# Sheet1.net
KiCad netlist of a schematic drawn in Altium Designer
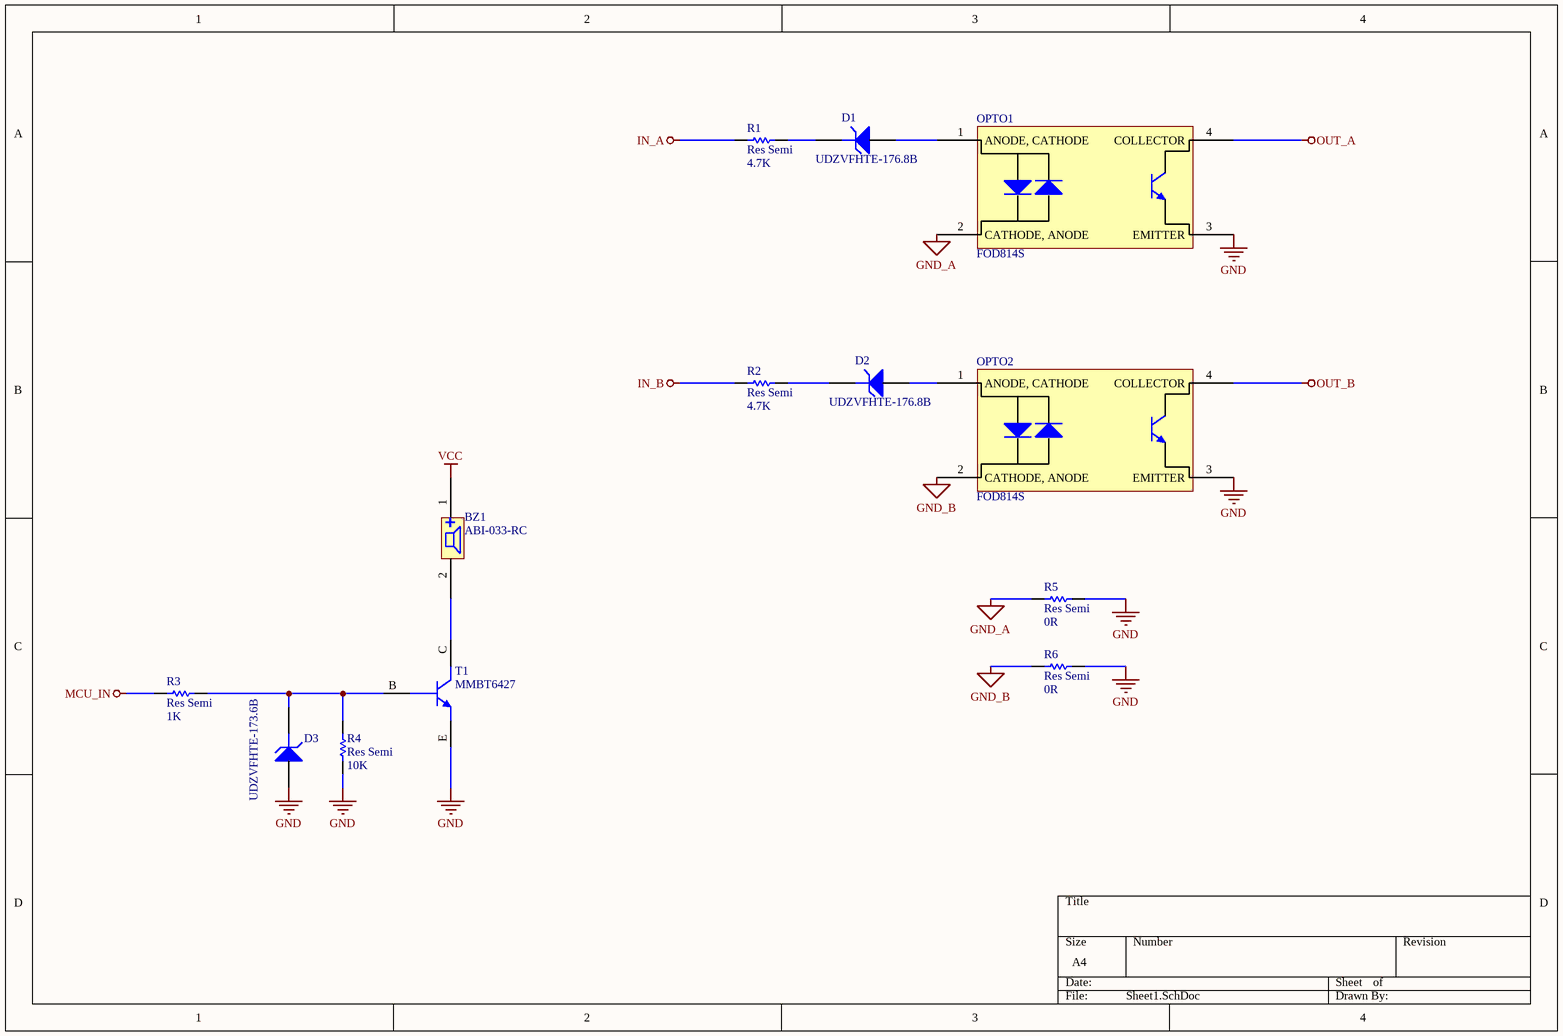
[diagram p0: Sheet1.SchDoc]

(export (version "E")
  (design (tool "Eeschema 10.0.6"))
  (components
    (comp (ref "BZ1")
      (value "ABI-033-RC")
      (footprint "ABI-033-RC")
      (fields (field (name "MANUFACTURER") "PRO SIGNAL"))
      (libsource (lib "BK4000TGLibraries") (part "ABI-033-RC"))
    )
    (comp (ref "D1")
      (value "UDZVFHTE-176.8B")
      (footprint "UDZVFHTE-176.8B")
      (libsource (lib "BK4000TGLibraries") (part "UDZVFHTE-176.8B"))
    )
    (comp (ref "D2")
      (value "UDZVFHTE-176.8B")
      (footprint "UDZVFHTE-176.8B")
      (libsource (lib "BK4000TGLibraries") (part "UDZVFHTE-176.8B"))
    )
    (comp (ref "D3")
      (value "UDZVFHTE-173.6B")
      (footprint "UDZVFHTE-176.8B")
      (libsource (lib "BK4000TGLibraries") (part "UDZVFHTE-176.8B"))
    )
    (comp (ref "OPTO1")
      (value "FOD814S")
      (footprint "FOD814")
      (description "AC Phototransistor Optocoupler")
      (fields (field (name "MANUFACTURER") "Fairchild Semiconductor"))
      (libsource (lib "FOD814") (part "FOD814S"))
    )
    (comp (ref "OPTO2")
      (value "FOD814S")
      (footprint "FOD814")
      (description "AC Phototransistor Optocoupler")
      (fields (field (name "MANUFACTURER") "Fairchild Semiconductor"))
      (libsource (lib "FOD814") (part "FOD814S"))
    )
    (comp (ref "R1")
      (value "Res Semi")
      (footprint "2012[0805]")
      (description "Semiconductor Resistor")
      (fields (field (name "ALTIUM_VALUE") "4.7K") (field (name "PUBLISHER") "Altium Limited"))
      (libsource (lib "Miscellaneous Devices") (part "Res Semi"))
    )
    (comp (ref "R2")
      (value "Res Semi")
      (footprint "2012[0805]")
      (description "Semiconductor Resistor")
      (fields (field (name "ALTIUM_VALUE") "4.7K") (field (name "PUBLISHER") "Altium Limited"))
      (libsource (lib "Miscellaneous Devices") (part "Res Semi"))
    )
    (comp (ref "R3")
      (value "Res Semi")
      (footprint "2012[0805]")
      (description "Semiconductor Resistor")
      (fields (field (name "ALTIUM_VALUE") "1K") (field (name "PUBLISHER") "Altium Limited"))
      (libsource (lib "Miscellaneous Devices") (part "Res Semi"))
    )
    (comp (ref "R4")
      (value "Res Semi")
      (footprint "2012[0805]")
      (description "Semiconductor Resistor")
      (fields (field (name "ALTIUM_VALUE") "10K") (field (name "PUBLISHER") "Altium Limited"))
      (libsource (lib "Miscellaneous Devices") (part "Res Semi"))
    )
    (comp (ref "R5")
      (value "Res Semi")
      (footprint "2012[0805]")
      (description "Semiconductor Resistor")
      (fields (field (name "ALTIUM_VALUE") "0R") (field (name "PUBLISHER") "Altium Limited"))
      (libsource (lib "Miscellaneous Devices") (part "Res Semi"))
    )
    (comp (ref "R6")
      (value "Res Semi")
      (footprint "2012[0805]")
      (description "Semiconductor Resistor")
      (fields (field (name "ALTIUM_VALUE") "0R") (field (name "PUBLISHER") "Altium Limited"))
      (libsource (lib "Miscellaneous Devices") (part "Res Semi"))
    )
    (comp (ref "T1")
      (value "MMBT6427")
      (footprint "MMBT6427")
      (fields (field (name "MANUFACTURER") "ON SEMICONDUCTOR/FAIRCHILD"))
      (libsource (lib "BK4000TGLibraries") (part "MMBT6427"))
    )
  )
  (nets
    (net (code "1") (name "GND") (class "Default")
      (node (ref "D3") (pin "2") (pinfunction "A_2") (pintype "passive"))
      (node (ref "OPTO1") (pin "3") (pinfunction "EMITTER_3") (pintype "passive"))
      (node (ref "OPTO2") (pin "3") (pinfunction "EMITTER_3") (pintype "passive"))
      (node (ref "R4") (pin "1") (pinfunction "1_1") (pintype "passive"))
      (node (ref "R5") (pin "2") (pinfunction "2_2") (pintype "passive"))
      (node (ref "R6") (pin "2") (pinfunction "2_2") (pintype "passive"))
      (node (ref "T1") (pin "E") (pinfunction "E_E") (pintype "passive"))
    )
    (net (code "2") (name "GND_A") (class "Default")
      (node (ref "OPTO1") (pin "2") (pinfunction "CATHODE,_ANODE_2") (pintype "passive"))
      (node (ref "R5") (pin "1") (pinfunction "1_1") (pintype "passive"))
    )
    (net (code "3") (name "GND_B") (class "Default")
      (node (ref "OPTO2") (pin "2") (pinfunction "CATHODE,_ANODE_2") (pintype "passive"))
      (node (ref "R6") (pin "1") (pinfunction "1_1") (pintype "passive"))
    )
    (net (code "4") (name "IN_A") (class "Default")
      (node (ref "R1") (pin "1") (pinfunction "1_1") (pintype "passive"))
    )
    (net (code "5") (name "IN_B") (class "Default")
      (node (ref "R2") (pin "1") (pinfunction "1_1") (pintype "passive"))
    )
    (net (code "6") (name "MCU_IN") (class "Default")
      (node (ref "R3") (pin "1") (pinfunction "1_1") (pintype "passive"))
    )
    (net (code "7") (name "Net-(BZ1-Pad2)") (class "Default")
      (node (ref "BZ1") (pin "2") (pinfunction "2_2") (pintype "passive"))
      (node (ref "T1") (pin "C") (pinfunction "C_C") (pintype "passive"))
    )
    (net (code "8") (name "Net-(D1-A)") (class "Default")
      (node (ref "D1") (pin "2") (pinfunction "A_2") (pintype "passive"))
      (node (ref "OPTO1") (pin "1") (pinfunction "ANODE,_CATHODE_1") (pintype "passive"))
    )
    (net (code "9") (name "Net-(D1-K)") (class "Default")
      (node (ref "D1") (pin "1") (pinfunction "K_1") (pintype "passive"))
      (node (ref "R1") (pin "2") (pinfunction "2_2") (pintype "passive"))
    )
    (net (code "10") (name "Net-(D2-A)") (class "Default")
      (node (ref "D2") (pin "2") (pinfunction "A_2") (pintype "passive"))
      (node (ref "OPTO2") (pin "1") (pinfunction "ANODE,_CATHODE_1") (pintype "passive"))
    )
    (net (code "11") (name "Net-(D2-K)") (class "Default")
      (node (ref "D2") (pin "1") (pinfunction "K_1") (pintype "passive"))
      (node (ref "R2") (pin "2") (pinfunction "2_2") (pintype "passive"))
    )
    (net (code "12") (name "Net-(D3-K)") (class "Default")
      (node (ref "D3") (pin "1") (pinfunction "K_1") (pintype "passive"))
      (node (ref "R3") (pin "2") (pinfunction "2_2") (pintype "passive"))
      (node (ref "R4") (pin "2") (pinfunction "2_2") (pintype "passive"))
      (node (ref "T1") (pin "B") (pinfunction "B_B") (pintype "passive"))
    )
    (net (code "13") (name "OUT_A") (class "Default")
      (node (ref "OPTO1") (pin "4") (pinfunction "COLLECTOR_4") (pintype "open_collector"))
    )
    (net (code "14") (name "OUT_B") (class "Default")
      (node (ref "OPTO2") (pin "4") (pinfunction "COLLECTOR_4") (pintype "open_collector"))
    )
    (net (code "15") (name "VCC") (class "Default")
      (node (ref "BZ1") (pin "1") (pinfunction "1_1") (pintype "passive"))
    )
  )
)
